# Phase_1.net
KiCad netlist of a schematic drawn in Altium Designer
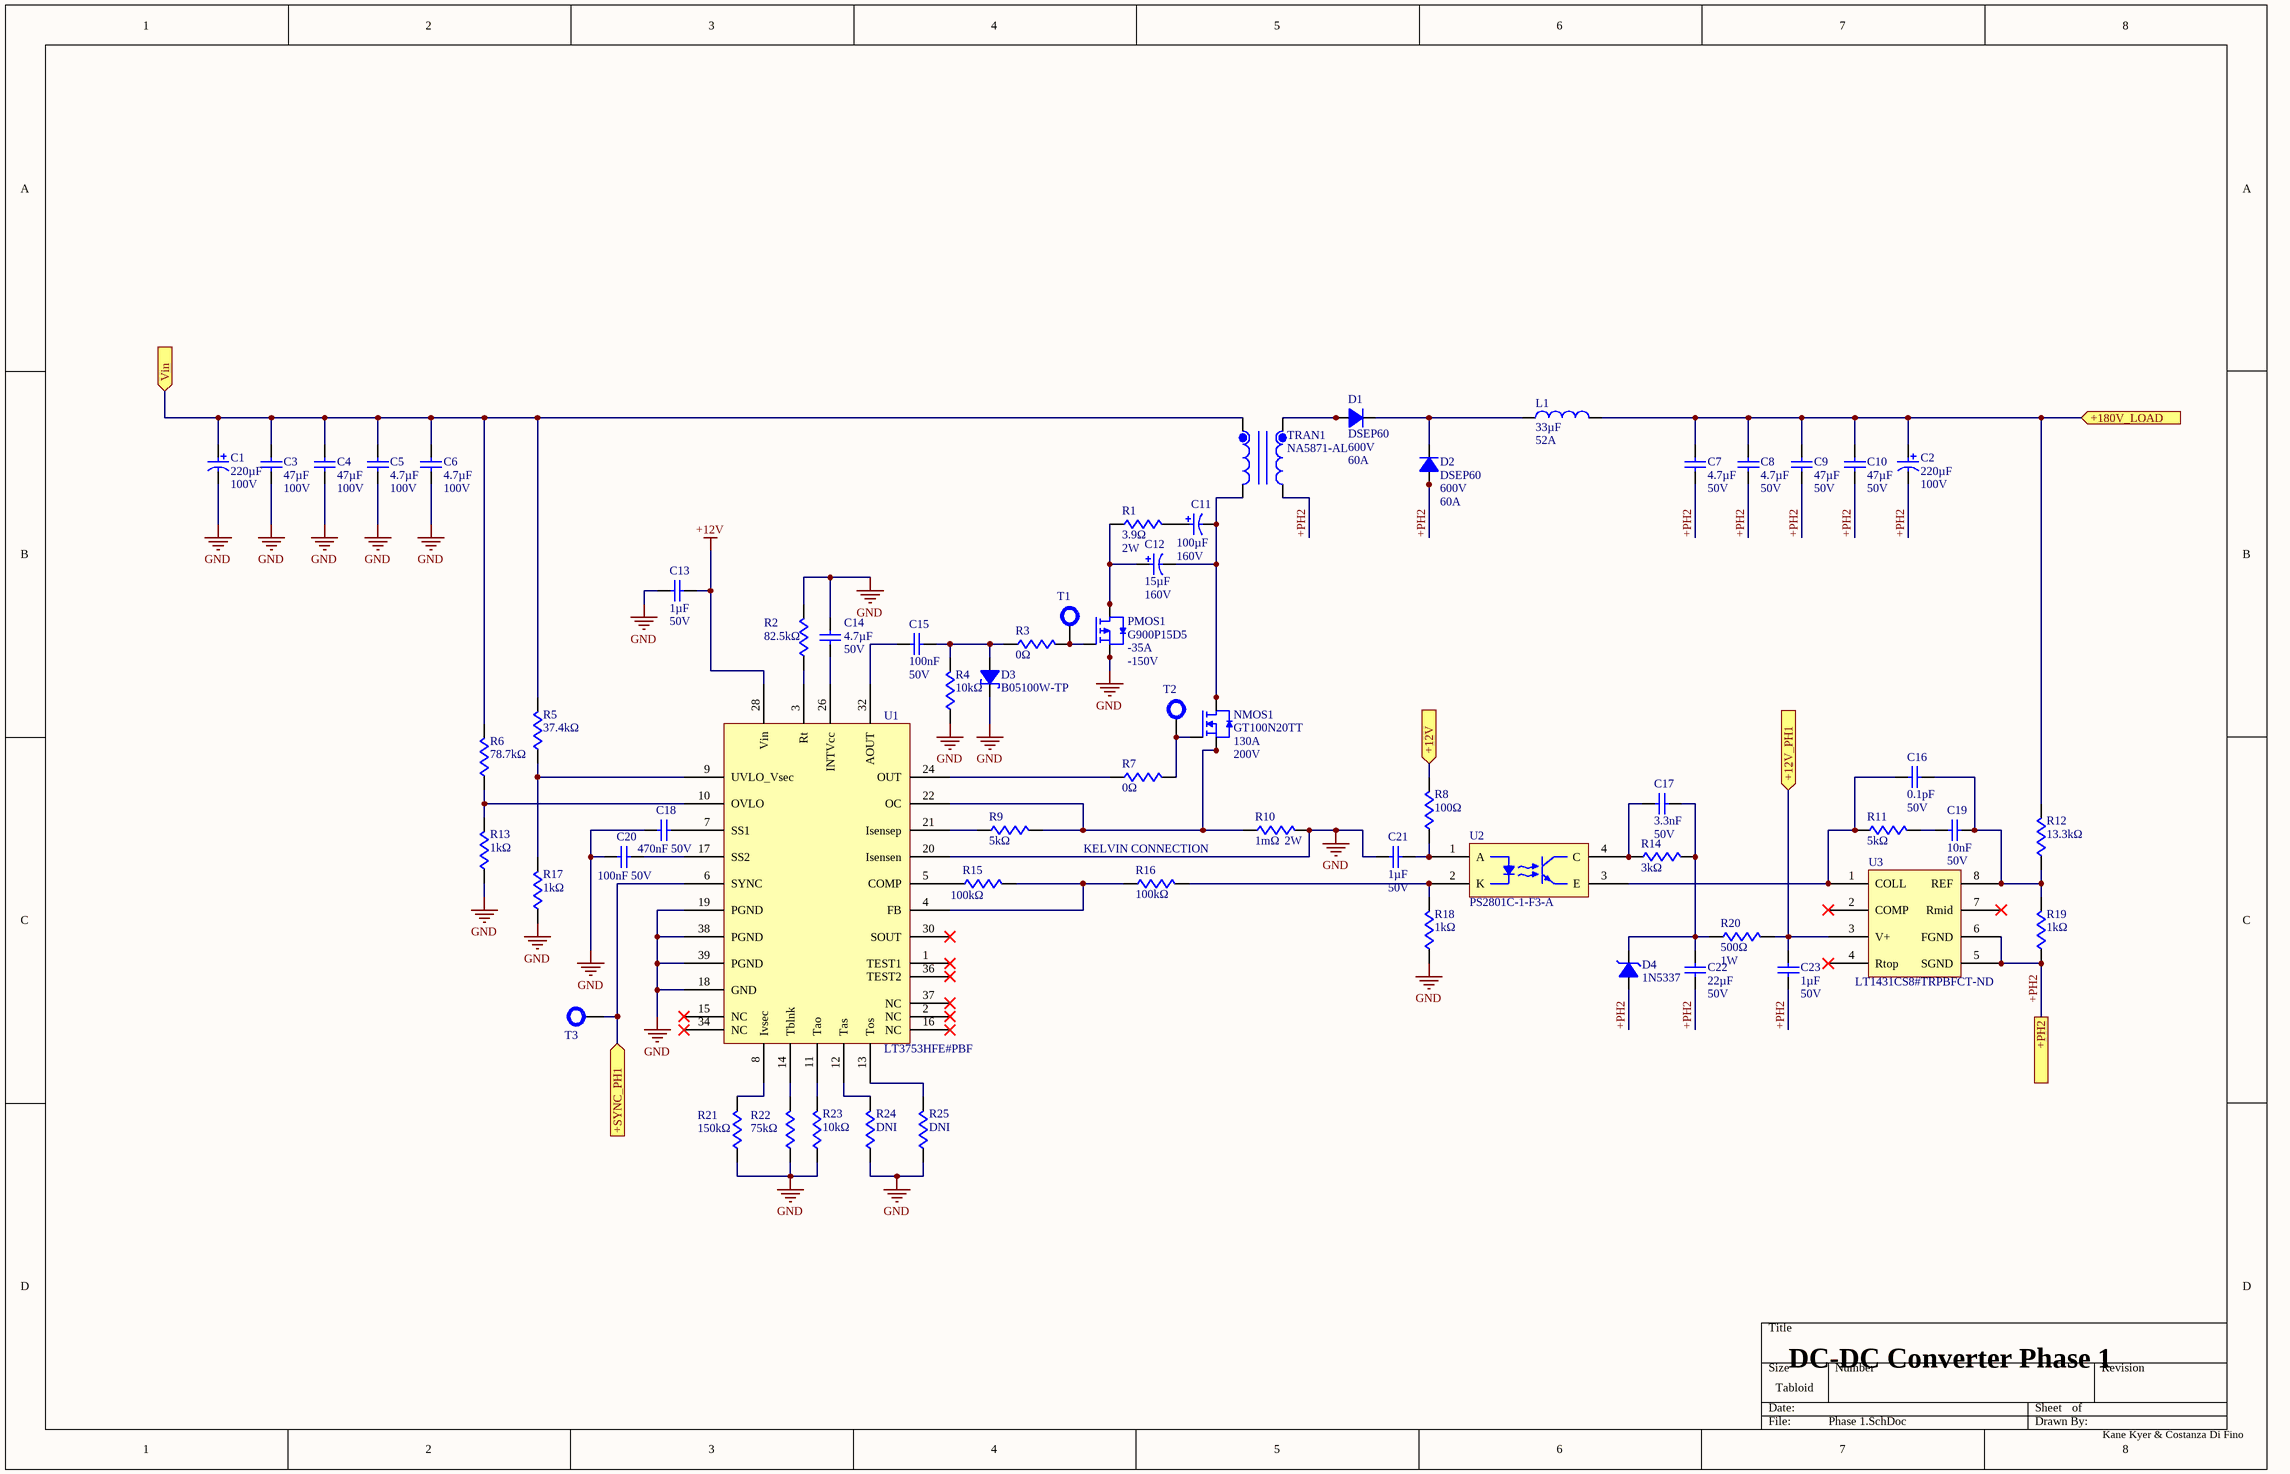
[diagram p0: Phase 1.SchDoc]

(export (version "E")
  (design (tool "Eeschema 10.0.6"))
  (components
    (comp (ref "C1")
      (value "220µF")
      (footprint "C_AEC")
      (description "Radial Can - SMD ALUMINUM ELECTROLYTIC CAPACITOR AFK 100V 220muF ±20% 0.709Dia 18.00mm")
      (fields
        (field (name "MANUFACTURER") "Cornell Dubilier")
        (field (name "MANUFACTURER PART NUMBER") "AFK227M2AR44T-F")
        (field (name "VOLTAGE RATING") "100V")
      )
      (libsource (lib "library") (part "AFK227M2AR44T-F"))
    )
    (comp (ref "C2")
      (value "220µF")
      (footprint "C_AEC")
      (description "Radial Can - SMD ALUMINUM ELECTROLYTIC CAPACITOR AFK 100V 220muF ±20% 0.709Dia 18.00mm")
      (fields
        (field (name "MANUFACTURER") "Cornell Dubilier")
        (field (name "MANUFACTURER PART NUMBER") "AFK227M2AR44T-F")
        (field (name "VOLTAGE RATING") "100V")
      )
      (libsource (lib "library") (part "AFK227M2AR44T-F"))
    )
    (comp (ref "C3")
      (value "47µF")
      (footprint "C_CAA573")
      (description "Multilayer Ceramic Chip Capacitors, Capacitance=47μF, LxWxT: 6.0x7.5x6.4mm")
      (fields
        (field (name "MANUFACTURER") "TDK")
        (field (name "MANUFACTURER PART NUMBER") "CAA573X7S2A476M640LH")
        (field (name "VOLTAGE RATING") "100V")
      )
      (libsource (lib "library") (part "CAA573X7S2A476M640LH"))
    )
    (comp (ref "C4")
      (value "47µF")
      (footprint "C_CAA573")
      (description "Multilayer Ceramic Chip Capacitors, Capacitance=47μF, LxWxT: 6.0x7.5x6.4mm")
      (fields
        (field (name "MANUFACTURER") "TDK")
        (field (name "MANUFACTURER PART NUMBER") "CAA573X7S2A476M640LH")
        (field (name "VOLTAGE RATING") "100V")
      )
      (libsource (lib "library") (part "CAA573X7S2A476M640LH"))
    )
    (comp (ref "C5")
      (value "4.7µF")
      (footprint "C_1210")
      (fields
        (field (name "MANUFACTURER") "Cal-Chip Electronics")
        (field (name "MANUFACTURER PART NUMBER") "GMC32X7S475K100NT")
        (field (name "VOLTAGE RATING (DC)") "100V")
      )
      (libsource (lib "library") (part "GMC32X7S475K100NT"))
    )
    (comp (ref "C6")
      (value "4.7µF")
      (footprint "C_1210")
      (fields
        (field (name "MANUFACTURER") "Cal-Chip Electronics")
        (field (name "MANUFACTURER PART NUMBER") "GMC32X7S475K100NT")
        (field (name "VOLTAGE RATING (DC)") "100V")
      )
      (libsource (lib "library") (part "GMC32X7S475K100NT"))
    )
    (comp (ref "C7")
      (value "4.7µF")
      (footprint "C_1206")
      (fields
        (field (name "MANUFACTURER") "Cal-Chip Electronics")
        (field (name "MANUFACTURER PART NUMBER") "GMC31X7R475K50NT")
        (field (name "VOLTAGE RATING (DC)") "50V")
      )
      (libsource (lib "library") (part "GMC31X7R475K50NT"))
    )
    (comp (ref "C8")
      (value "4.7µF")
      (footprint "C_1206")
      (fields
        (field (name "MANUFACTURER") "Cal-Chip Electronics")
        (field (name "MANUFACTURER PART NUMBER") "GMC31X7R475K50NT")
        (field (name "VOLTAGE RATING (DC)") "50V")
      )
      (libsource (lib "library") (part "GMC31X7R475K50NT"))
    )
    (comp (ref "C9")
      (value "47µF")
      (footprint "C_CKG57N")
      (fields
        (field (name "MANUFACTURER") "TDK")
        (field (name "MANUFACTURER PART NUMBER") "CKG57NX7R1H476M500JJ")
        (field (name "VOLTAGE RATING (DC)") "50V")
      )
      (libsource (lib "library") (part "CKG57NX7R1H476M500JJ"))
    )
    (comp (ref "C10")
      (value "47µF")
      (footprint "C_CKG57N")
      (fields
        (field (name "MANUFACTURER") "TDK")
        (field (name "MANUFACTURER PART NUMBER") "CKG57NX7R1H476M500JJ")
        (field (name "VOLTAGE RATING (DC)") "50V")
      )
      (libsource (lib "library") (part "CKG57NX7R1H476M500JJ"))
    )
    (comp (ref "C11")
      (value "100µF")
      (footprint "UUJ2C101MNJ1MS")
      (description "Aluminum Electrolytic Capacitors 100 F 160 V Radial, SMD 5000 Hrs 105C")
      (fields
        (field (name "MANUFACTURER") "Nichicon")
        (field (name "MANUFACTURER PART NUMBER") "UUJ2C101MNJ1MS")
        (field (name "VOLTAGE RATING (DC)") "160V")
      )
      (libsource (lib "library") (part "UUJ2C101MNJ1MS"))
    )
    (comp (ref "C12")
      (value "15µF")
      (footprint "ULT2C150MNL1GS")
      (description "Radial Can - SMD ALUMINUM ELECTROLYTIC CAPACITOR ULT 160V 15muF ±20% 0.315Dia 8.00mm")
      (fields
        (field (name "MANUFACTURER") "Nichicon")
        (field (name "MANUFACTURER PART NUMBER") "ULT2C150MNL1GS")
        (field (name "VOLTAGE") "160V")
      )
      (libsource (lib "library") (part "ULT2C150MNL1GS"))
    )
    (comp (ref "C13")
      (value "1µF")
      (footprint "C_0805")
      (description "50V 1uF X7R ±10% 0805 Multilayer Ceramic Capacitors MLCC - SMD/SMT ROHS")
      (fields
        (field (name "MANUFACTURER") "Samsung Electro-Mechanics")
        (field (name "MANUFACTURER PART NUMBER") "CL21B105KBFNNNE")
        (field (name "VOLTAGE") "50V")
      )
      (libsource (lib "library") (part "CL21B105KBFNNNE"))
    )
    (comp (ref "C14")
      (value "4.7µF")
      (footprint "C_1206")
      (fields
        (field (name "MANUFACTURER") "Cal-Chip Electronics")
        (field (name "MANUFACTURER PART NUMBER") "GMC31X7R475K50NT")
        (field (name "VOLTAGE RATING (DC)") "50V")
      )
      (libsource (lib "library") (part "GMC31X7R475K50NT"))
    )
    (comp (ref "C15")
      (value "100nF")
      (footprint "C_0603")
      (description "50V 100nF X7R ±10% 0603 Multilayer Ceramic Capacitors MLCC - SMD/SMT ROHS")
      (fields
        (field (name "MANUFACTURER") "KEMET")
        (field (name "MANUFACTURER PART NUMBER") "C0603C104K5RACTU")
        (field (name "VOLTAGE RATING") "50V")
      )
      (libsource (lib "library") (part "C0603C104K5RACTU"))
    )
    (comp (ref "C16")
      (value "0.1pF")
      (footprint "C_0402")
      (description "Multilayer Ceramic Capacitor, 0.1 pF, 50 V, ± 0.05pF, C0G (NP0), 0402 [1005 Metric]")
      (fields
        (field (name "MANUFACTURER") "Murata")
        (field (name "MANUFACTURER PART NUMBER") "GJM1555C1HR10WB01D")
        (field (name "VOLTAGE RATING") "50V")
      )
      (libsource (lib "library") (part "GJM1555C1HR10WB01D"))
    )
    (comp (ref "C17")
      (value "3.3nF")
      (footprint "C_0603")
      (description "50V 3.3nF C0G ±1% 0603 Multilayer Ceramic Capacitors MLCC - SMD/SMT ROHS")
      (fields
        (field (name "MANUFACTURER") "Murata")
        (field (name "MANUFACTURER PART NUMBER") "GCM1885C1H332FA16D")
        (field (name "VOLTAGE RATING") "50V")
      )
      (libsource (lib "library") (part "GCM1885C1H332FA16D"))
    )
    (comp (ref "C18")
      (value "470nF")
      (footprint "C_0402")
      (description "50V 470nF X5R ±10% 0402 Multilayer Ceramic Capacitors MLCC - SMD/SMT ROHS")
      (fields
        (field (name "MANUFACTURER") "Murata")
        (field (name "MANUFACTURER PART NUMBER") "GRM155R61H474KE11D")
        (field (name "VOLTAGE RATING") "50V")
      )
      (libsource (lib "library") (part "GRM155R61H474KE11D"))
    )
    (comp (ref "C19")
      (value "10nF")
      (footprint "C_0603")
      (description "Capacitor, Multilayer, Ceramic, 50V, 10%, X7R, 15% Tc, 0.01Uf, Surface Mount, 0603")
      (fields
        (field (name "MANUFACTURER") "KEMET")
        (field (name "MANUFACTURER PART NUMBER") "C0603C103K5RACTU")
        (field (name "VOLTAGE RATING") "50V")
      )
      (libsource (lib "library") (part "C0603C103K5RACTU"))
    )
    (comp (ref "C20")
      (value "100nF")
      (footprint "C_0603")
      (description "50V 100nF X7R ±10% 0603 Multilayer Ceramic Capacitors MLCC - SMD/SMT ROHS")
      (fields
        (field (name "MANUFACTURER") "KEMET")
        (field (name "MANUFACTURER PART NUMBER") "C0603C104K5RACTU")
        (field (name "VOLTAGE RATING") "50V")
      )
      (libsource (lib "library") (part "C0603C104K5RACTU"))
    )
    (comp (ref "C21")
      (value "1µF")
      (footprint "C_0805")
      (description "50V 1uF X7R ±10% 0805 Multilayer Ceramic Capacitors MLCC - SMD/SMT ROHS")
      (fields
        (field (name "MANUFACTURER") "Samsung Electro-Mechanics")
        (field (name "MANUFACTURER PART NUMBER") "CL21B105KBFNNNE")
        (field (name "VOLTAGE") "50V")
      )
      (libsource (lib "library") (part "CL21B105KBFNNNE"))
    )
    (comp (ref "C22")
      (value "22µF")
      (footprint "C_2220")
      (fields
        (field (name "MANUFACTURER") "Cal-Chip Electronics")
        (field (name "MANUFACTURER PART NUMBER") "GMC55X7R226M50NT")
        (field (name "VOLTAGE RATING (DC)") "50V")
      )
      (libsource (lib "library") (part "GMC55X7R226M50NT"))
    )
    (comp (ref "C23")
      (value "1µF")
      (footprint "C_0805")
      (description "50V 1uF X7R ±10% 0805 Multilayer Ceramic Capacitors MLCC - SMD/SMT ROHS")
      (fields
        (field (name "MANUFACTURER") "Samsung Electro-Mechanics")
        (field (name "MANUFACTURER PART NUMBER") "CL21B105KBFNNNE")
        (field (name "VOLTAGE") "50V")
      )
      (libsource (lib "library") (part "CL21B105KBFNNNE"))
    )
    (comp (ref "D1")
      (value "DSEP60")
      (footprint "D_DSEP60")
      (description "Power Diode Discretes-FRED TO-")
      (fields
        (field (name "MANUFACTURER") "IXYS")
        (field (name "MANUFACTURER PART NUMBER") "DSEP60-06AZ-TRL")
        (field (name "VR") "600V")
        (field (name "IO") "60A")
      )
      (libsource (lib "library") (part "DSEP60-06AZ-TRL"))
    )
    (comp (ref "D2")
      (value "DSEP60")
      (footprint "D_DSEP60")
      (description "Power Diode Discretes-FRED TO-")
      (fields
        (field (name "MANUFACTURER") "IXYS")
        (field (name "MANUFACTURER PART NUMBER") "DSEP60-06AZ-TRL")
        (field (name "VR") "600V")
        (field (name "IO") "60A")
      )
      (libsource (lib "library") (part "DSEP60-06AZ-TRL"))
    )
    (comp (ref "D3")
      (value "B05100W-TP")
      (footprint "D_B05100W")
      (description "Rectifier Diode, Schottky, 1 Phase, 1 Element, 0.5A, 100V V(RRM), Silicon")
      (fields (field (name "MANUFACTURER") "MCC") (field (name "MANUFACTURER PART NUMBER") "B05100W-TP"))
      (libsource (lib "library") (part "B05100W-TP"))
    )
    (comp (ref "D4")
      (value "1N5337BRLG")
      (footprint "D_1N5337")
      (description "Zener Diode Single 4.7V 5% 2Ohm 5000mW 2-Pin Case 017AA-01 T/R / DIODE ZENER 4.7V 5W AXIAL")
      (fields
        (field (name "MANUFACTURER") "onsemi")
        (field (name "TOLERANCE") "5%")
        (field (name "SUPPLIER PART NUMBER") "1N5337")
      )
      (libsource (lib "library") (part "1N5337BRLG"))
    )
    (comp (ref "L1")
      (value "33µF")
      (footprint "CPEX4141L-330MC")
      (description "Fixed Ind 33UH 52A 1.88 Mohm Th")
      (fields
        (field (name "MANUFACTURER") "Codaca")
        (field (name "MANUFACTURER PART NUMBER") "CPEX4141L-330MC")
        (field (name "IRMS") "52A")
      )
      (libsource (lib "library") (part "CPEX4141L-330MC"))
    )
    (comp (ref "NMOS1")
      (value "GT100N20TT")
      (footprint "GT100N20TT")
      (description "Mosfet N-ch 200V 130A 280W Tolt")
      (fields
        (field (name "MANUFACTURER") "GoFord")
        (field (name "MANUFACTURER PART NUMBER") "GT100N20TT")
        (field (name "ID") "130A")
        (field (name "VDS") "200V")
      )
      (libsource (lib "library") (part "GT100N20TT"))
    )
    (comp (ref "PMOS1")
      (value "G900P15D5")
      (footprint "G900P15")
      (description "P-150V, -60A, RD(max) Less Than 80mOhm at -10V, VTH -1V to -4V, DFN5x6-8L")
      (fields
        (field (name "MANUFACTURER") "GoFord")
        (field (name "MANUFACTURER PART NUMBER") "G900P15D5")
        (field (name "ID") "-35A")
        (field (name "VDS") "-150V")
      )
      (libsource (lib "library") (part "G900P15D5"))
    )
    (comp (ref "R1")
      (value "3.9Ω")
      (footprint "R_SM2W")
      (description "SM Series 3.9 Ohm ±5 % 2 W ±200 ppm/°C Surface Mount Wirewound Resistor")
      (fields
        (field (name "MANUFACTURER") "TE Connectivity")
        (field (name "MANUFACTURER PART NUMBER") "SMW23R9JT")
        (field (name "POWER RATING") "2W")
      )
      (libsource (lib "library") (part "SMW23R9JT"))
    )
    (comp (ref "R2")
      (value "82.5kΩ")
      (footprint "R_0805")
      (description "Res Thick Film 0805 82.5K Ohm 1% 1/8W ±100ppm/°C Molded SMD SMD Paper T/R")
      (fields
        (field (name "MANUFACTURER") "Stackpole Electronics")
        (field (name "MANUFACTURER PART NUMBER") "RMCF0805FT82K5")
      )
      (libsource (lib "library") (part "RMCF0805FT82K5"))
    )
    (comp (ref "R3")
      (value "0Ω")
      (footprint "R_0805")
      (description "Zero Ohm Resistor, Jumper, 0805 [2012 Metric], Thick Film, 125 mW, 2.5 A, Surface Mount Device")
      (fields
        (field (name "MANUFACTURER") "Vishay")
        (field (name "MANUFACTURER PART NUMBER") "CRCW08050000Z0EA")
      )
      (libsource (lib "library") (part "CRCW08050000Z0EA"))
    )
    (comp (ref "R4")
      (value "10kΩ")
      (footprint "R_0402")
      (description "Fixed Resistor, Metal Glaze/thick Film, 0.0625W, 10000ohm, 50V, 1% +/-Tol, Surface Mount, 0402")
      (fields
        (field (name "MANUFACTURER") "Cal-Chip Electronics")
        (field (name "MANUFACTURER PART NUMBER") "RM04F1002CT")
      )
      (libsource (lib "library") (part "RM04F1002CT"))
    )
    (comp (ref "R5")
      (value "37.4kΩ")
      (footprint "R_0603")
      (description "100mW Thick Film Resistors 75V ±100ppm/℃ ±1% 37.4kΩ 0603 Chip Resistor - Surface Mount ROHS")
      (fields
        (field (name "MANUFACTURER") "Yageo Group")
        (field (name "MANUFACTURER PART NUMBER") "RC0603FR-0737K4L")
      )
      (libsource (lib "library") (part "RC0603FR-0737K4L"))
    )
    (comp (ref "R6")
      (value "78.7kΩ")
      (footprint "R_0603")
      (description "Res Thick Film 0603 78.7K Ohm 1% 0.1W(1/10W) ±100ppm/C Pad SMD T/R")
      (fields
        (field (name "MANUFACTURER") "Yageo Group")
        (field (name "MANUFACTURER PART NUMBER") "RC0603FR-0778K7L")
      )
      (libsource (lib "library") (part "RC0603FR-0778K7L"))
    )
    (comp (ref "R7")
      (value "0Ω")
      (footprint "R_0805")
      (description "Zero Ohm Resistor, Jumper, 0805 [2012 Metric], Thick Film, 125 mW, 2.5 A, Surface Mount Device")
      (fields
        (field (name "MANUFACTURER") "Vishay")
        (field (name "MANUFACTURER PART NUMBER") "CRCW08050000Z0EA")
      )
      (libsource (lib "library") (part "CRCW08050000Z0EA"))
    )
    (comp (ref "R8")
      (value "100Ω")
      (footprint "R_0603")
      (description "Yageo RC0603FR-07100RL 0603 SMD Resistor 100 Ohm thin film chip resistor")
      (fields
        (field (name "MANUFACTURER") "Yageo Group")
        (field (name "MANUFACTURER PART NUMBER") "RC0603FR-07100RL")
      )
      (libsource (lib "library") (part "RC0603FR-07100RL"))
    )
    (comp (ref "R9")
      (value "5kΩ")
      (footprint "R_0402")
      (description "Res Thin Film 0402 5K Ohm 0.1% 0.05W(1/20W) +/-25ppm/C Sulfur Resistant Pad SMD Medical T/R")
      (fields
        (field (name "MANUFACTURER") "Vishay")
        (field (name "MANUFACTURER PART NUMBER") "PNM0402E5001BST1")
      )
      (libsource (lib "library") (part "PNM0402E5001BST1"))
    )
    (comp (ref "R10")
      (value "1mΩ")
      (footprint "R_2512")
      (description "Res Thick Film 2512 1m Ohm 1% 2W ±75ppm/°C Molded SMD Embossed T/R")
      (fields
        (field (name "MANUFACTURER") "Bourns")
        (field (name "MANUFACTURER PART NUMBER") "CRE2512-FZ-R001E-2")
        (field (name "POWER RATING") "2W")
      )
      (libsource (lib "library") (part "CRE2512-FZ-R001E-2"))
    )
    (comp (ref "R11")
      (value "5kΩ")
      (footprint "R_0402")
      (description "Res Thin Film 0402 5K Ohm 0.1% 0.05W(1/20W) +/-25ppm/C Sulfur Resistant Pad SMD Medical T/R")
      (fields
        (field (name "MANUFACTURER") "Vishay")
        (field (name "MANUFACTURER PART NUMBER") "PNM0402E5001BST1")
      )
      (libsource (lib "library") (part "PNM0402E5001BST1"))
    )
    (comp (ref "R12")
      (value "13.3kΩ")
      (footprint "R_0603")
      (description "Res Thick Film 0603 13.3K Ohm 1% 0.1W(1/10W) ±100ppm/C Pad SMD Automotive T/R")
      (fields
        (field (name "MANUFACTURER") "Stackpole Electronics")
        (field (name "MANUFACTURER PART NUMBER") "RMCF0603FT13K3")
      )
      (libsource (lib "library") (part "RMCF0603FT13K3"))
    )
    (comp (ref "R13")
      (value "1kΩ")
      (footprint "R_0402")
      (description "62.5mW Thick Film Resistors ±100ppm/℃ ±1% 1kΩ 0402 Chip Resistor - Surface Mount ROHS")
      (fields
        (field (name "MANUFACTURER") "Cal-Chip Electronics")
        (field (name "MANUFACTURER PART NUMBER") "RM04F1001CT")
      )
      (libsource (lib "library") (part "RM04F1001CT"))
    )
    (comp (ref "R14")
      (value "3kΩ")
      (footprint "C_0402")
      (description "Res Thick Film 0402 3K Ohm 1% 0.063W(1/16W) ±100ppm/C Pad SMD Automotive T/R")
      (fields
        (field (name "MANUFACTURER") "Yageo Group")
        (field (name "MANUFACTURER PART NUMBER") "AC0402FR-073KL")
      )
      (libsource (lib "library") (part "AC0402FR-073KL"))
    )
    (comp (ref "R15")
      (value "100kΩ")
      (footprint "R_0402")
      (description "Fixed Resistor, Metal Glaze/thick Film, 0.0625W, 100000ohm, 50V, 1% +/-Tol, Surface Mount, 0402")
      (fields
        (field (name "MANUFACTURER") "Cal-Chip Electronics")
        (field (name "MANUFACTURER PART NUMBER") "RM04F1003CT")
      )
      (libsource (lib "library") (part "RM04F1003CT"))
    )
    (comp (ref "R16")
      (value "100kΩ")
      (footprint "R_0402")
      (description "Fixed Resistor, Metal Glaze/thick Film, 0.0625W, 100000ohm, 50V, 1% +/-Tol, Surface Mount, 0402")
      (fields
        (field (name "MANUFACTURER") "Cal-Chip Electronics")
        (field (name "MANUFACTURER PART NUMBER") "RM04F1003CT")
      )
      (libsource (lib "library") (part "RM04F1003CT"))
    )
    (comp (ref "R17")
      (value "1kΩ")
      (footprint "R_0402")
      (description "62.5mW Thick Film Resistors ±100ppm/℃ ±1% 1kΩ 0402 Chip Resistor - Surface Mount ROHS")
      (fields
        (field (name "MANUFACTURER") "Cal-Chip Electronics")
        (field (name "MANUFACTURER PART NUMBER") "RM04F1001CT")
      )
      (libsource (lib "library") (part "RM04F1001CT"))
    )
    (comp (ref "R18")
      (value "1kΩ")
      (footprint "R_0402")
      (description "62.5mW Thick Film Resistors ±100ppm/℃ ±1% 1kΩ 0402 Chip Resistor - Surface Mount ROHS")
      (fields
        (field (name "MANUFACTURER") "Cal-Chip Electronics")
        (field (name "MANUFACTURER PART NUMBER") "RM04F1001CT")
      )
      (libsource (lib "library") (part "RM04F1001CT"))
    )
    (comp (ref "R19")
      (value "1kΩ")
      (footprint "R_0402")
      (description "62.5mW Thick Film Resistors ±100ppm/℃ ±1% 1kΩ 0402 Chip Resistor - Surface Mount ROHS")
      (fields
        (field (name "MANUFACTURER") "Cal-Chip Electronics")
        (field (name "MANUFACTURER PART NUMBER") "RM04F1001CT")
      )
      (libsource (lib "library") (part "RM04F1001CT"))
    )
    (comp (ref "R20")
      (value "500Ω")
      (footprint "R_WSC2515")
      (description "Fixed Resistor, Wire Wound, 1W, 500ohm, 22.3607V, 1% +/-Tol, 20ppm/Cel, Surface Mount, 2515")
      (fields
        (field (name "MANUFACTURER") "Vishay")
        (field (name "MANUFACTURER PART NUMBER") "WSC2515500R0FEB")
        (field (name "POWER RATING") "1W")
      )
      (libsource (lib "library") (part "WSC2515500R0FEB"))
    )
    (comp (ref "R21")
      (value "150kΩ")
      (footprint "R_0603")
      (description "100mW Thick Film Resistors 75V ±100ppm/℃ ±1% 150kΩ 0603 Chip Resistor - Surface Mount ROHS")
      (fields
        (field (name "MANUFACTURER") "Yageo Group")
        (field (name "MANUFACTURER PART NUMBER") "RC0603FR-07150KL")
      )
      (libsource (lib "library") (part "RC0603FR-07150KL"))
    )
    (comp (ref "R22")
      (value "75kΩ")
      (footprint "R_0603")
      (description "Res Thick Film 0603 75K Ohm 1% 0.1W(1/10W) ±100ppm/C Pad SMD T/R Automotive AEC-Q200")
      (fields
        (field (name "MANUFACTURER") "Yageo Group")
        (field (name "MANUFACTURER PART NUMBER") "AC0603FR-0775KL")
      )
      (libsource (lib "library") (part "AC0603FR-0775KL"))
    )
    (comp (ref "R23")
      (value "10kΩ")
      (footprint "R_0402")
      (description "Fixed Resistor, Metal Glaze/thick Film, 0.0625W, 10000ohm, 50V, 1% +/-Tol, Surface Mount, 0402")
      (fields
        (field (name "MANUFACTURER") "Cal-Chip Electronics")
        (field (name "MANUFACTURER PART NUMBER") "RM04F1002CT")
      )
      (libsource (lib "library") (part "RM04F1002CT"))
    )
    (comp (ref "R24")
      (value "DNI")
      (footprint "R_0805")
      (description "Zero Ohm Resistor, Jumper, 0805 [2012 Metric], Thick Film, 125 mW, 2.5 A, Surface Mount Device")
      (fields
        (field (name "MANUFACTURER") "Vishay")
        (field (name "MANUFACTURER PART NUMBER") "CRCW08050000Z0EA")
      )
      (libsource (lib "library") (part "CRCW08050000Z0EA"))
    )
    (comp (ref "R25")
      (value "DNI")
      (footprint "R_0805")
      (description "Zero Ohm Resistor, Jumper, 0805 [2012 Metric], Thick Film, 125 mW, 2.5 A, Surface Mount Device")
      (fields
        (field (name "MANUFACTURER") "Vishay")
        (field (name "MANUFACTURER PART NUMBER") "CRCW08050000Z0EA")
      )
      (libsource (lib "library") (part "CRCW08050000Z0EA"))
    )
    (comp (ref "T1") (value "TEST") (footprint "TEST_POINT") (libsource (lib "library") (part "TEST")))
    (comp (ref "T2") (value "TEST") (footprint "TEST_POINT") (libsource (lib "library") (part "TEST")))
    (comp (ref "T3") (value "TEST") (footprint "TEST_POINT") (libsource (lib "library") (part "TEST")))
    (comp (ref "TRAN1")
      (value "NA5871-AL")
      (footprint "NA5871-AL")
      (description "Transformer, planar, for TI UCC28950, SMT, RoHS")
      (fields (field (name "MANUFACTURER") "Coilcraft") (field (name "SUPPLIER PART NUMBER") "NA5871-AL"))
      (libsource (lib "library") (part "NA5871-AL"))
    )
    (comp (ref "U1")
      (value "LT3753HFE#PBF")
      (footprint "LT3753")
      (description "500kHz 8.5V~100V Buck-boost type 1 TSSOP-38-EP-4.4mm DC-DC Controllers ROHS")
      (fields
        (field (name "MANUFACTURER") "Analog Devices")
        (field (name "MANUFACTURER PART NUMBER") "LT3753HFE#PBF")
      )
      (libsource (lib "library") (part "LT3753HFE#PBF"))
    )
    (comp (ref "U2")
      (value "PS2801C-1-F3-A")
      (footprint "PS2801C")
      (description "Optocoupler DC-IN 1-CH Transistor DC-OUT 4-Pin SSOP T/R")
      (fields
        (field (name "MANUFACTURER") "Renesas")
        (field (name "MANUFACTURER PART NUMBER") "PS2801C-1-F3-A")
      )
      (libsource (lib "library") (part "PS2801C-1-F3-A"))
    )
    (comp (ref "U3")
      (value "LT1431CS8#TRPBF")
      (footprint "LT1431")
      (description "V-Ref Adjustable 2.5V to 36V 100mA 8-Pin SOIC N T/R")
      (fields
        (field (name "SUPPLIER PART NUMBER") "LT1431CS8#TRPBFCT-ND")
        (field (name "MANUFACTURER") "Analog Devices")
        (field (name "TOLERANCE") "0.4%")
      )
      (libsource (lib "library") (part "LT1431CS8#TRPBF"))
    )
  )
  (nets
    (net (code "1") (name "+12V") (class "Default")
      (node (ref "C13") (pin "2") (pintype "passive"))
      (node (ref "R8") (pin "2") (pintype "passive"))
      (node (ref "U1") (pin "28") (pinfunction "Vin_28") (pintype "passive"))
    )
    (net (code "2") (name "/+12V_PH1") (class "Default")
      (node (ref "C23") (pin "2") (pintype "passive"))
      (node (ref "R20") (pin "2") (pintype "passive"))
      (node (ref "U3") (pin "3") (pinfunction "V+_3") (pintype "passive"))
    )
    (net (code "3") (name "/+180V_LOAD") (class "Default")
      (node (ref "C10") (pin "2") (pintype "passive"))
      (node (ref "C2") (pin "1") (pintype "passive"))
      (node (ref "C7") (pin "2") (pintype "passive"))
      (node (ref "C8") (pin "2") (pintype "passive"))
      (node (ref "C9") (pin "2") (pintype "passive"))
      (node (ref "L1") (pin "2") (pintype "passive"))
      (node (ref "R12") (pin "2") (pintype "passive"))
    )
    (net (code "4") (name "/+PH2") (class "Default")
      (node (ref "C10") (pin "1") (pintype "passive"))
      (node (ref "C2") (pin "2") (pintype "passive"))
      (node (ref "C22") (pin "1") (pintype "passive"))
      (node (ref "C23") (pin "1") (pintype "passive"))
      (node (ref "C7") (pin "1") (pintype "passive"))
      (node (ref "C8") (pin "1") (pintype "passive"))
      (node (ref "C9") (pin "1") (pintype "passive"))
      (node (ref "D2") (pin "1") (pinfunction "A_1") (pintype "passive"))
      (node (ref "D2") (pin "3") (pinfunction "A_3") (pintype "passive"))
      (node (ref "D4") (pin "2") (pintype "passive"))
      (node (ref "R19") (pin "1") (pintype "passive"))
      (node (ref "TRAN1") (pin "11") (pintype "passive"))
      (node (ref "U3") (pin "5") (pinfunction "SGND_5") (pintype "passive"))
      (node (ref "U3") (pin "6") (pinfunction "FGND_6") (pintype "passive"))
    )
    (net (code "5") (name "/+SYNC_PH1") (class "Default")
      (node (ref "T3") (pin "1") (pinfunction "1_1") (pintype "passive"))
      (node (ref "U1") (pin "6") (pinfunction "SYNC_6") (pintype "passive"))
    )
    (net (code "6") (name "/Vin") (class "Default")
      (node (ref "C1") (pin "1") (pintype "passive"))
      (node (ref "C3") (pin "2") (pintype "passive"))
      (node (ref "C4") (pin "2") (pintype "passive"))
      (node (ref "C5") (pin "2") (pintype "passive"))
      (node (ref "C6") (pin "2") (pintype "passive"))
      (node (ref "R5") (pin "2") (pintype "passive"))
      (node (ref "R6") (pin "2") (pintype "passive"))
      (node (ref "TRAN1") (pin "1") (pintype "passive"))
    )
    (net (code "7") (name "GND") (class "Default")
      (node (ref "C1") (pin "2") (pintype "passive"))
      (node (ref "C13") (pin "1") (pintype "passive"))
      (node (ref "C14") (pin "1") (pintype "passive"))
      (node (ref "C18") (pin "1") (pintype "passive"))
      (node (ref "C20") (pin "1") (pintype "passive"))
      (node (ref "C21") (pin "1") (pintype "passive"))
      (node (ref "C3") (pin "1") (pintype "passive"))
      (node (ref "C4") (pin "1") (pintype "passive"))
      (node (ref "C5") (pin "1") (pintype "passive"))
      (node (ref "C6") (pin "1") (pintype "passive"))
      (node (ref "D3") (pin "1") (pintype "passive"))
      (node (ref "PMOS1") (pin "1") (pinfunction "S_1") (pintype "passive"))
      (node (ref "PMOS1") (pin "2") (pinfunction "S_2") (pintype "passive"))
      (node (ref "PMOS1") (pin "3") (pinfunction "S_3") (pintype "passive"))
      (node (ref "R10") (pin "2") (pintype "passive"))
      (node (ref "R13") (pin "1") (pintype "passive"))
      (node (ref "R17") (pin "1") (pintype "passive"))
      (node (ref "R18") (pin "1") (pintype "passive"))
      (node (ref "R2") (pin "2") (pintype "passive"))
      (node (ref "R21") (pin "1") (pintype "passive"))
      (node (ref "R22") (pin "1") (pintype "passive"))
      (node (ref "R23") (pin "1") (pintype "passive"))
      (node (ref "R24") (pin "1") (pintype "passive"))
      (node (ref "R25") (pin "1") (pintype "passive"))
      (node (ref "R4") (pin "1") (pintype "passive"))
      (node (ref "U1") (pin "18") (pinfunction "GND_18") (pintype "passive"))
      (node (ref "U1") (pin "19") (pinfunction "PGND_19") (pintype "passive"))
      (node (ref "U1") (pin "20") (pinfunction "Isensen_20") (pintype "passive"))
      (node (ref "U1") (pin "38") (pinfunction "PGND_38") (pintype "passive"))
      (node (ref "U1") (pin "39") (pinfunction "PGND_39") (pintype "passive"))
    )
    (net (code "8") (name "Net-(C11-Pad1)") (class "Default")
      (node (ref "C11") (pin "1") (pintype "passive"))
      (node (ref "R1") (pin "2") (pintype "passive"))
    )
    (net (code "9") (name "Net-(C11-Pad2)") (class "Default")
      (node (ref "C11") (pin "2") (pintype "passive"))
      (node (ref "C12") (pin "2") (pintype "passive"))
      (node (ref "NMOS1") (pin "10") (pinfunction "D_10") (pintype "passive"))
      (node (ref "NMOS1") (pin "11") (pinfunction "D_11") (pintype "passive"))
      (node (ref "NMOS1") (pin "12") (pinfunction "D_12") (pintype "passive"))
      (node (ref "NMOS1") (pin "13") (pinfunction "D_13") (pintype "passive"))
      (node (ref "NMOS1") (pin "14") (pinfunction "D_14") (pintype "passive"))
      (node (ref "NMOS1") (pin "15") (pinfunction "D_15") (pintype "passive"))
      (node (ref "NMOS1") (pin "16") (pinfunction "D_16") (pintype "passive"))
      (node (ref "NMOS1") (pin "9") (pinfunction "D_9") (pintype "passive"))
      (node (ref "TRAN1") (pin "4") (pintype "passive"))
    )
    (net (code "10") (name "Net-(C12-Pad1)") (class "Default")
      (node (ref "C12") (pin "1") (pintype "passive"))
      (node (ref "PMOS1") (pin "5") (pinfunction "D_5") (pintype "passive"))
      (node (ref "PMOS1") (pin "6") (pinfunction "D_6") (pintype "passive"))
      (node (ref "PMOS1") (pin "7") (pinfunction "D_7") (pintype "passive"))
      (node (ref "PMOS1") (pin "8") (pinfunction "D_8") (pintype "passive"))
      (node (ref "R1") (pin "1") (pintype "passive"))
    )
    (net (code "11") (name "Net-(C15-Pad2)") (class "Default")
      (node (ref "C15") (pin "2") (pintype "passive"))
      (node (ref "D3") (pin "2") (pintype "passive"))
      (node (ref "R3") (pin "1") (pintype "passive"))
      (node (ref "R4") (pin "2") (pintype "passive"))
    )
    (net (code "12") (name "Net-(C17-Pad2)") (class "Default")
      (node (ref "C17") (pin "2") (pintype "passive"))
      (node (ref "C22") (pin "2") (pintype "passive"))
      (node (ref "D4") (pin "1") (pintype "passive"))
      (node (ref "R14") (pin "2") (pintype "passive"))
      (node (ref "R20") (pin "1") (pintype "passive"))
    )
    (net (code "13") (name "Net-(C19-Pad1)") (class "Default")
      (node (ref "C19") (pin "1") (pintype "passive"))
      (node (ref "R11") (pin "2") (pintype "passive"))
    )
    (net (code "14") (name "Net-(D1-A-Pad1)") (class "Default")
      (node (ref "D1") (pin "1") (pinfunction "A_1") (pintype "passive"))
      (node (ref "D1") (pin "3") (pinfunction "A_3") (pintype "passive"))
      (node (ref "TRAN1") (pin "6") (pintype "passive"))
    )
    (net (code "15") (name "Net-(D1-C)") (class "Default")
      (node (ref "D1") (pin "4") (pinfunction "C_4") (pintype "passive"))
      (node (ref "D2") (pin "4") (pinfunction "C_4") (pintype "passive"))
      (node (ref "L1") (pin "1") (pintype "passive"))
    )
    (net (code "16") (name "Net-(NMOS1-G)") (class "Default")
      (node (ref "NMOS1") (pin "8") (pinfunction "G_8") (pintype "passive"))
      (node (ref "R7") (pin "2") (pintype "passive"))
      (node (ref "T2") (pin "1") (pinfunction "1_1") (pintype "passive"))
    )
    (net (code "17") (name "Net-(PMOS1-G)") (class "Default")
      (node (ref "PMOS1") (pin "4") (pinfunction "G_4") (pintype "passive"))
      (node (ref "R3") (pin "2") (pintype "passive"))
      (node (ref "T1") (pin "1") (pinfunction "1_1") (pintype "passive"))
    )
    (net (code "18") (name "Net-(U1-AOUT)") (class "Default")
      (node (ref "C15") (pin "1") (pintype "passive"))
      (node (ref "U1") (pin "32") (pinfunction "AOUT_32") (pintype "passive"))
    )
    (net (code "19") (name "Net-(U1-COMP)") (class "Default")
      (node (ref "R15") (pin "1") (pintype "passive"))
      (node (ref "U1") (pin "5") (pinfunction "COMP_5") (pintype "passive"))
    )
    (net (code "20") (name "Net-(U1-FB)") (class "Default")
      (node (ref "R15") (pin "2") (pintype "passive"))
      (node (ref "R16") (pin "1") (pintype "passive"))
      (node (ref "U1") (pin "4") (pinfunction "FB_4") (pintype "passive"))
    )
    (net (code "21") (name "Net-(U1-INTVcc)") (class "Default")
      (node (ref "C14") (pin "2") (pintype "passive"))
      (node (ref "U1") (pin "26") (pinfunction "INTVcc_26") (pintype "passive"))
    )
    (net (code "22") (name "Net-(U1-Isensep)") (class "Default")
      (node (ref "R9") (pin "1") (pintype "passive"))
      (node (ref "U1") (pin "21") (pinfunction "Isensep_21") (pintype "passive"))
    )
    (net (code "23") (name "Net-(U1-Ivsec)") (class "Default")
      (node (ref "R21") (pin "2") (pintype "passive"))
      (node (ref "U1") (pin "8") (pinfunction "Ivsec_8") (pintype "passive"))
    )
    (net (code "24") (name "Net-(U1-OC)") (class "Default")
      (node (ref "NMOS1") (pin "1") (pinfunction "S_1") (pintype "passive"))
      (node (ref "NMOS1") (pin "2") (pinfunction "S_2") (pintype "passive"))
      (node (ref "NMOS1") (pin "3") (pinfunction "S_3") (pintype "passive"))
      (node (ref "NMOS1") (pin "4") (pinfunction "S_4") (pintype "passive"))
      (node (ref "NMOS1") (pin "5") (pinfunction "S_5") (pintype "passive"))
      (node (ref "NMOS1") (pin "6") (pinfunction "S_6") (pintype "passive"))
      (node (ref "NMOS1") (pin "7") (pinfunction "S_7") (pintype "passive"))
      (node (ref "R10") (pin "1") (pintype "passive"))
      (node (ref "R9") (pin "2") (pintype "passive"))
      (node (ref "U1") (pin "22") (pinfunction "OC_22") (pintype "passive"))
    )
    (net (code "25") (name "Net-(U1-OUT)") (class "Default")
      (node (ref "R7") (pin "1") (pintype "passive"))
      (node (ref "U1") (pin "24") (pinfunction "OUT_24") (pintype "passive"))
    )
    (net (code "26") (name "Net-(U1-OVLO)") (class "Default")
      (node (ref "R13") (pin "2") (pintype "passive"))
      (node (ref "R6") (pin "1") (pintype "passive"))
      (node (ref "U1") (pin "10") (pinfunction "OVLO_10") (pintype "passive"))
    )
    (net (code "27") (name "Net-(U1-Rt)") (class "Default")
      (node (ref "R2") (pin "1") (pintype "passive"))
      (node (ref "U1") (pin "3") (pinfunction "Rt_3") (pintype "passive"))
    )
    (net (code "28") (name "Net-(U1-SS1)") (class "Default")
      (node (ref "C18") (pin "2") (pintype "passive"))
      (node (ref "U1") (pin "7") (pinfunction "SS1_7") (pintype "passive"))
    )
    (net (code "29") (name "Net-(U1-SS2)") (class "Default")
      (node (ref "C20") (pin "2") (pintype "passive"))
      (node (ref "U1") (pin "17") (pinfunction "SS2_17") (pintype "passive"))
    )
    (net (code "30") (name "Net-(U1-Tao)") (class "Default")
      (node (ref "R23") (pin "2") (pintype "passive"))
      (node (ref "U1") (pin "11") (pinfunction "Tao_11") (pintype "passive"))
    )
    (net (code "31") (name "Net-(U1-Tas)") (class "Default")
      (node (ref "R24") (pin "2") (pintype "passive"))
      (node (ref "U1") (pin "12") (pinfunction "Tas_12") (pintype "passive"))
    )
    (net (code "32") (name "Net-(U1-Tblnk)") (class "Default")
      (node (ref "R22") (pin "2") (pintype "passive"))
      (node (ref "U1") (pin "14") (pinfunction "Tblnk_14") (pintype "passive"))
    )
    (net (code "33") (name "Net-(U1-Tos)") (class "Default")
      (node (ref "R25") (pin "2") (pintype "passive"))
      (node (ref "U1") (pin "13") (pinfunction "Tos_13") (pintype "passive"))
    )
    (net (code "34") (name "Net-(U1-UVLO_Vsec)") (class "Default")
      (node (ref "R17") (pin "2") (pintype "passive"))
      (node (ref "R5") (pin "1") (pintype "passive"))
      (node (ref "U1") (pin "9") (pinfunction "UVLO_Vsec_9") (pintype "passive"))
    )
    (net (code "35") (name "Net-(U2-A)") (class "Default")
      (node (ref "C21") (pin "2") (pintype "passive"))
      (node (ref "R8") (pin "1") (pintype "passive"))
      (node (ref "U2") (pin "1") (pinfunction "A_1") (pintype "passive"))
    )
    (net (code "36") (name "Net-(U2-C)") (class "Default")
      (node (ref "C17") (pin "1") (pintype "passive"))
      (node (ref "R14") (pin "1") (pintype "passive"))
      (node (ref "U2") (pin "4") (pinfunction "C_4") (pintype "passive"))
    )
    (net (code "37") (name "Net-(U2-E)") (class "Default")
      (node (ref "C16") (pin "1") (pintype "passive"))
      (node (ref "R11") (pin "1") (pintype "passive"))
      (node (ref "U2") (pin "3") (pinfunction "E_3") (pintype "passive"))
      (node (ref "U3") (pin "1") (pinfunction "COLL_1") (pintype "passive"))
    )
    (net (code "38") (name "Net-(U2-K)") (class "Default")
      (node (ref "R16") (pin "2") (pintype "passive"))
      (node (ref "R18") (pin "2") (pintype "passive"))
      (node (ref "U2") (pin "2") (pinfunction "K_2") (pintype "passive"))
    )
    (net (code "39") (name "Net-(U3-REF)") (class "Default")
      (node (ref "C16") (pin "2") (pintype "passive"))
      (node (ref "C19") (pin "2") (pintype "passive"))
      (node (ref "R12") (pin "1") (pintype "passive"))
      (node (ref "R19") (pin "2") (pintype "passive"))
      (node (ref "U3") (pin "8") (pinfunction "REF_8") (pintype "passive"))
    )
    (net (code "40") (name "unconnected-(U1-NC-Pad2)") (class "Default")
      (node (ref "U1") (pin "2") (pinfunction "NC_2") (pintype "passive+no_connect"))
    )
    (net (code "41") (name "unconnected-(U1-NC-Pad15)") (class "Default")
      (node (ref "U1") (pin "15") (pinfunction "NC_15") (pintype "passive+no_connect"))
    )
    (net (code "42") (name "unconnected-(U1-NC-Pad16)") (class "Default")
      (node (ref "U1") (pin "16") (pinfunction "NC_16") (pintype "passive+no_connect"))
    )
    (net (code "43") (name "unconnected-(U1-NC-Pad34)") (class "Default")
      (node (ref "U1") (pin "34") (pinfunction "NC_34") (pintype "passive+no_connect"))
    )
    (net (code "44") (name "unconnected-(U1-NC-Pad37)") (class "Default")
      (node (ref "U1") (pin "37") (pinfunction "NC_37") (pintype "passive+no_connect"))
    )
    (net (code "45") (name "unconnected-(U1-SOUT-Pad30)") (class "Default")
      (node (ref "U1") (pin "30") (pinfunction "SOUT_30") (pintype "passive+no_connect"))
    )
    (net (code "46") (name "unconnected-(U1-TEST1-Pad1)") (class "Default")
      (node (ref "U1") (pin "1") (pinfunction "TEST1_1") (pintype "passive+no_connect"))
    )
    (net (code "47") (name "unconnected-(U1-TEST2-Pad36)") (class "Default")
      (node (ref "U1") (pin "36") (pinfunction "TEST2_36") (pintype "passive+no_connect"))
    )
    (net (code "48") (name "unconnected-(U3-COMP-Pad2)") (class "Default")
      (node (ref "U3") (pin "2") (pinfunction "COMP_2") (pintype "passive+no_connect"))
    )
    (net (code "49") (name "unconnected-(U3-Rmid-Pad7)") (class "Default")
      (node (ref "U3") (pin "7") (pinfunction "Rmid_7") (pintype "passive+no_connect"))
    )
    (net (code "50") (name "unconnected-(U3-Rtop-Pad4)") (class "Default")
      (node (ref "U3") (pin "4") (pinfunction "Rtop_4") (pintype "passive+no_connect"))
    )
  )
)
